# RTC-board.net
KiCad netlist of a schematic drawn in EAGLE
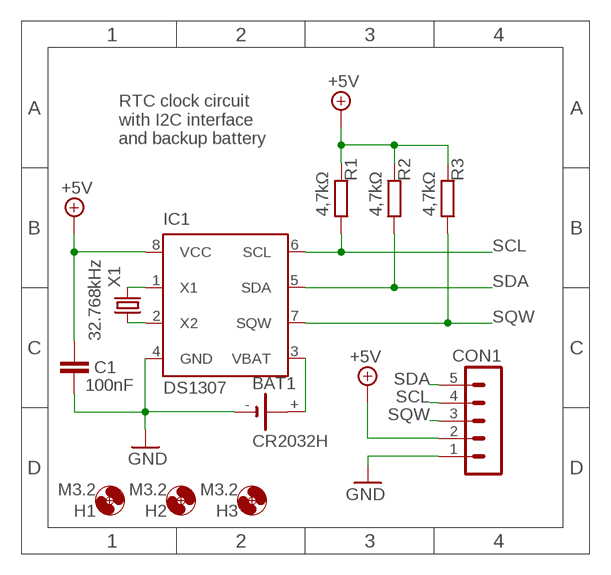
[diagram p0: schematic, sheet 1]

(export (version "E")
  (design (tool "Eeschema 10.0.6"))
  (components
    (comp (ref "BAT1")
      (value "CR2032H")
      (footprint "eagle-import:CR2032H")
      (libsource (lib "eagle-import") (part "CR2032H"))
    )
    (comp (ref "C1")
      (value "100nF")
      (footprint "eagle-import:C050-025X075")
      (libsource (lib "eagle-import") (part "C-EU050-025X075"))
    )
    (comp (ref "CON1")
      (value "MA05-1")
      (footprint "eagle-import:MA05-1")
      (libsource (lib "eagle-import") (part "MA05-1"))
    )
    (comp (ref "H1")
      (value "M3.2")
      (footprint "eagle-import:3,2")
      (libsource (lib "eagle-import") (part "MOUNT-HOLE3.2"))
    )
    (comp (ref "H2")
      (value "M3.2")
      (footprint "eagle-import:3,2")
      (libsource (lib "eagle-import") (part "MOUNT-HOLE3.2"))
    )
    (comp (ref "H3")
      (value "M3.2")
      (footprint "eagle-import:3,2")
      (libsource (lib "eagle-import") (part "MOUNT-HOLE3.2"))
    )
    (comp (ref "IC1")
      (value "DS1307")
      (footprint "eagle-import:DIL08")
      (libsource (lib "eagle-import") (part "DS1307"))
    )
    (comp (ref "R1")
      (value "4,7kΩ")
      (footprint "eagle-import:0207_7")
      (libsource (lib "eagle-import") (part "R-EU_0207/7"))
    )
    (comp (ref "R2")
      (value "4,7kΩ")
      (footprint "eagle-import:0207_7")
      (libsource (lib "eagle-import") (part "R-EU_0207/7"))
    )
    (comp (ref "R3")
      (value "4,7kΩ")
      (footprint "eagle-import:0207_7")
      (libsource (lib "eagle-import") (part "R-EU_0207/7"))
    )
    (comp (ref "X1")
      (value "32.768kHz")
      (footprint "eagle-import:TC38H")
      (libsource (lib "eagle-import") (part "CRYSTALTC38H"))
    )
  )
  (nets
    (net (code "1") (name "+5V") (class "Default")
      (node (ref "C1") (pin "1") (pinfunction "1_1") (pintype "passive"))
      (node (ref "CON1") (pin "2") (pinfunction "2_2") (pintype "passive"))
      (node (ref "IC1") (pin "8") (pinfunction "VCC_8") (pintype "power_in"))
      (node (ref "R1") (pin "2") (pinfunction "2_2") (pintype "passive"))
      (node (ref "R2") (pin "2") (pinfunction "2_2") (pintype "passive"))
      (node (ref "R3") (pin "2") (pinfunction "2_2") (pintype "passive"))
    )
    (net (code "2") (name "/SCL") (class "Default")
      (node (ref "CON1") (pin "4") (pinfunction "4_4") (pintype "passive"))
      (node (ref "IC1") (pin "6") (pinfunction "SCL_6") (pintype "input"))
      (node (ref "R1") (pin "1") (pinfunction "1_1") (pintype "passive"))
    )
    (net (code "3") (name "/SDA") (class "Default")
      (node (ref "CON1") (pin "5") (pinfunction "5_5") (pintype "passive"))
      (node (ref "IC1") (pin "5") (pinfunction "SDA_5") (pintype "bidirectional"))
      (node (ref "R2") (pin "1") (pinfunction "1_1") (pintype "passive"))
    )
    (net (code "4") (name "/SQW") (class "Default")
      (node (ref "CON1") (pin "3") (pinfunction "3_3") (pintype "passive"))
      (node (ref "IC1") (pin "7") (pinfunction "SQW_7") (pintype "open_collector"))
      (node (ref "R3") (pin "1") (pinfunction "1_1") (pintype "passive"))
    )
    (net (code "5") (name "GND") (class "Default")
      (node (ref "BAT1") (pin "-") (pinfunction "-_-") (pintype "passive"))
      (node (ref "C1") (pin "2") (pinfunction "2_2") (pintype "passive"))
      (node (ref "CON1") (pin "1") (pinfunction "1_1") (pintype "passive"))
      (node (ref "IC1") (pin "4") (pinfunction "GND_4") (pintype "power_in"))
    )
    (net (code "6") (name "Net-(IC1-VBAT)") (class "Default")
      (node (ref "BAT1") (pin "+") (pinfunction "+_+") (pintype "passive"))
      (node (ref "IC1") (pin "3") (pinfunction "VBAT_3") (pintype "passive"))
    )
    (net (code "7") (name "Net-(IC1-X1)") (class "Default")
      (node (ref "IC1") (pin "1") (pinfunction "X1_1") (pintype "input"))
      (node (ref "X1") (pin "2") (pinfunction "2_2") (pintype "passive"))
    )
    (net (code "8") (name "Net-(IC1-X2)") (class "Default")
      (node (ref "IC1") (pin "2") (pinfunction "X2_2") (pintype "output"))
      (node (ref "X1") (pin "1") (pinfunction "1_1") (pintype "passive"))
    )
  )
)
